# svf.net
KiCad netlist of a schematic drawn in EAGLE
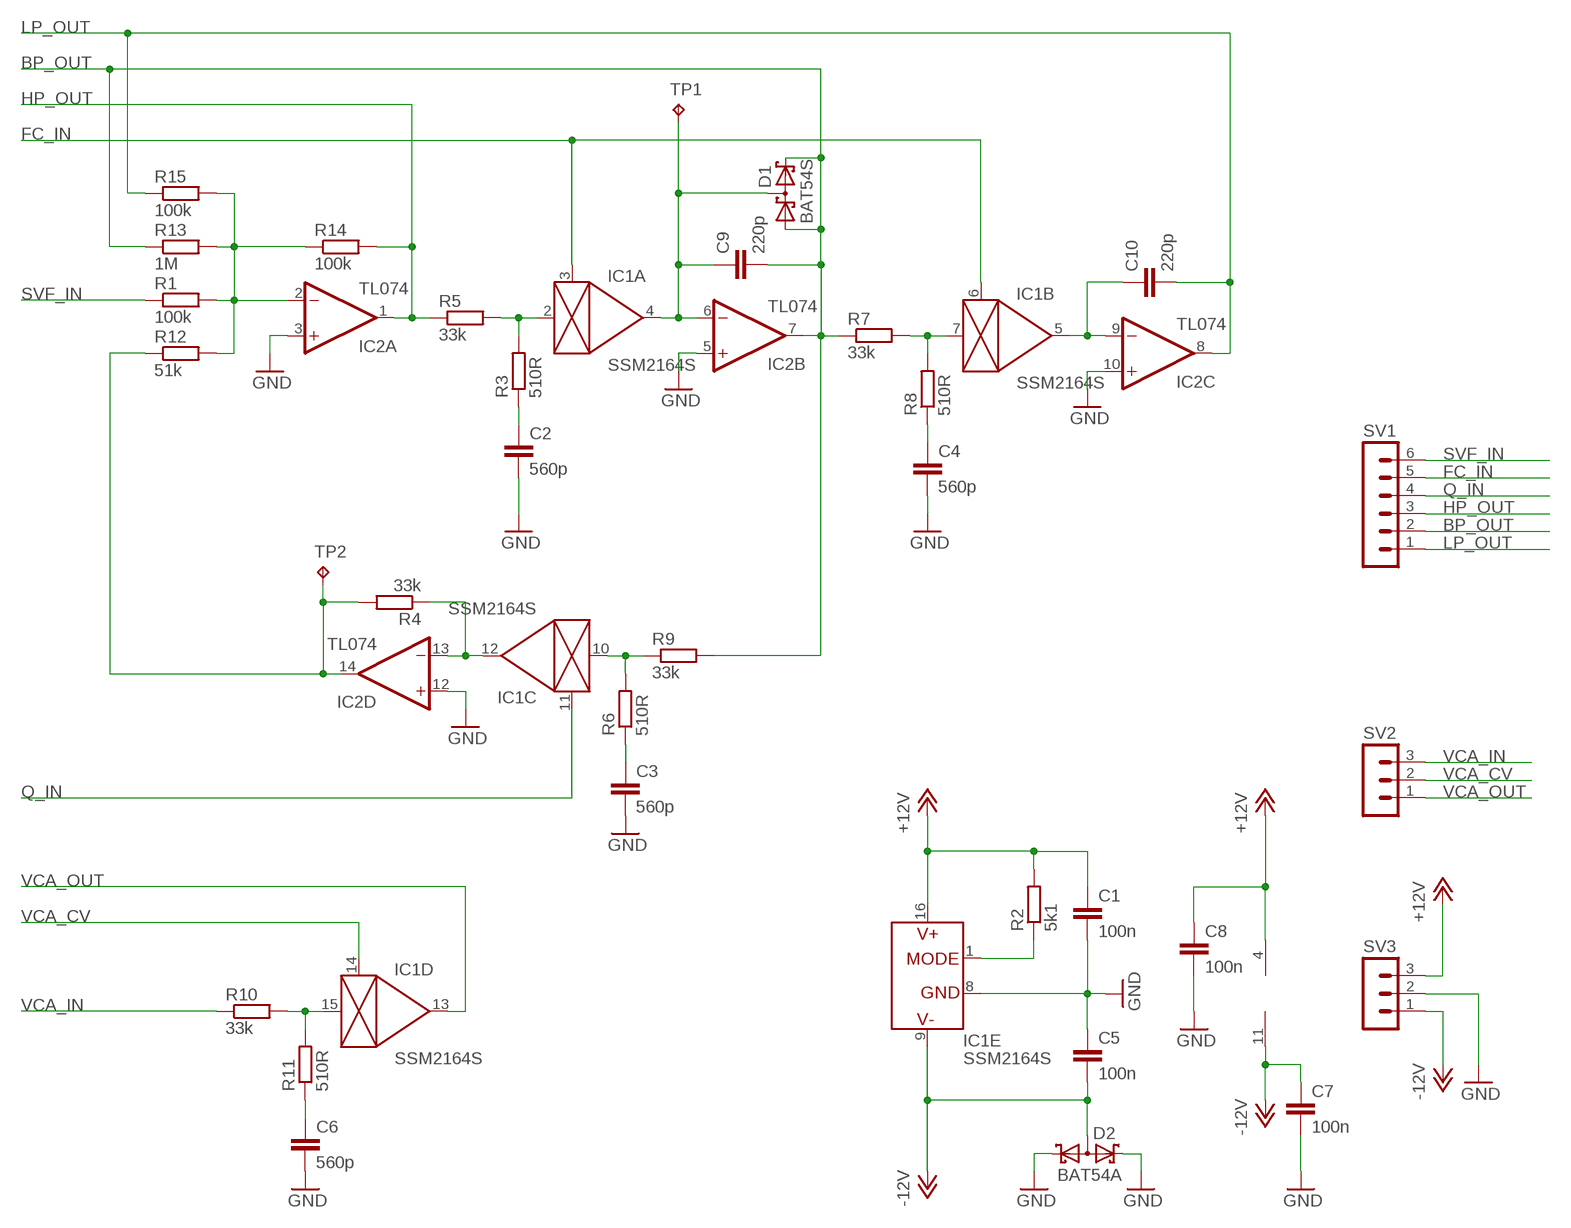
[diagram p0: schematic, sheet 1]

(export (version "E")
  (design (tool "Eeschema 10.0.6"))
  (components
    (comp (ref "C1")
      (value "100n")
      (footprint "eagle-import:C0603")
      (libsource (lib "eagle-import") (part "C-EUC0603"))
    )
    (comp (ref "C2")
      (value "560p")
      (footprint "eagle-import:C0603")
      (libsource (lib "eagle-import") (part "C-EUC0603"))
    )
    (comp (ref "C3")
      (value "560p")
      (footprint "eagle-import:C0603")
      (libsource (lib "eagle-import") (part "C-EUC0603"))
    )
    (comp (ref "C4")
      (value "560p")
      (footprint "eagle-import:C0603")
      (libsource (lib "eagle-import") (part "C-EUC0603"))
    )
    (comp (ref "C5")
      (value "100n")
      (footprint "eagle-import:C0603")
      (libsource (lib "eagle-import") (part "C-EUC0603"))
    )
    (comp (ref "C6")
      (value "560p")
      (footprint "eagle-import:C0603")
      (libsource (lib "eagle-import") (part "C-EUC0603"))
    )
    (comp (ref "C7")
      (value "100n")
      (footprint "eagle-import:C0603")
      (libsource (lib "eagle-import") (part "C-EUC0603"))
    )
    (comp (ref "C8")
      (value "100n")
      (footprint "eagle-import:C0603")
      (libsource (lib "eagle-import") (part "C-EUC0603"))
    )
    (comp (ref "C9")
      (value "220p")
      (footprint "eagle-import:C0603")
      (libsource (lib "eagle-import") (part "C-EUC0603"))
    )
    (comp (ref "C10")
      (value "220p")
      (footprint "eagle-import:C0603")
      (libsource (lib "eagle-import") (part "C-EUC0603"))
    )
    (comp (ref "D1")
      (value "BAT54S")
      (footprint "eagle-import:SOT23")
      (libsource (lib "eagle-import") (part "BAT54S"))
    )
    (comp (ref "D2")
      (value "BAT54A")
      (footprint "eagle-import:SOT23")
      (libsource (lib "eagle-import") (part "BAT54A"))
    )
    (comp (ref "IC1")
      (value "SSM2164S")
      (footprint "eagle-import:SOIC16N")
      (libsource (lib "eagle-import") (part "SSM2164S"))
    )
    (comp (ref "IC2")
      (value "TL074")
      (footprint "eagle-import:SO14")
      (libsource (lib "eagle-import") (part "TL074D"))
    )
    (comp (ref "R1")
      (value "100k")
      (footprint "eagle-import:0603")
      (libsource (lib "eagle-import") (part "R-EU_0603"))
    )
    (comp (ref "R2")
      (value "5k1")
      (footprint "eagle-import:0603")
      (libsource (lib "eagle-import") (part "R-EU_0603"))
    )
    (comp (ref "R3")
      (value "510R")
      (footprint "eagle-import:0603")
      (libsource (lib "eagle-import") (part "R-EU_0603"))
    )
    (comp (ref "R4")
      (value "33k")
      (footprint "eagle-import:0603")
      (libsource (lib "eagle-import") (part "R-EU_0603"))
    )
    (comp (ref "R5")
      (value "33k")
      (footprint "eagle-import:0603")
      (libsource (lib "eagle-import") (part "R-EU_0603"))
    )
    (comp (ref "R6")
      (value "510R")
      (footprint "eagle-import:0603")
      (libsource (lib "eagle-import") (part "R-EU_0603"))
    )
    (comp (ref "R7")
      (value "33k")
      (footprint "eagle-import:0603")
      (libsource (lib "eagle-import") (part "R-EU_0603"))
    )
    (comp (ref "R8")
      (value "510R")
      (footprint "eagle-import:0603")
      (libsource (lib "eagle-import") (part "R-EU_0603"))
    )
    (comp (ref "R9")
      (value "33k")
      (footprint "eagle-import:0603")
      (libsource (lib "eagle-import") (part "R-EU_0603"))
    )
    (comp (ref "R10")
      (value "33k")
      (footprint "eagle-import:0603")
      (libsource (lib "eagle-import") (part "R-EU_0603"))
    )
    (comp (ref "R11")
      (value "510R")
      (footprint "eagle-import:0603")
      (libsource (lib "eagle-import") (part "R-EU_0603"))
    )
    (comp (ref "R12")
      (value "51k")
      (footprint "eagle-import:0603")
      (libsource (lib "eagle-import") (part "R-EU_0603"))
    )
    (comp (ref "R13")
      (value "1M")
      (footprint "eagle-import:0603")
      (libsource (lib "eagle-import") (part "R-EU_0603"))
    )
    (comp (ref "R14")
      (value "100k")
      (footprint "eagle-import:0603")
      (libsource (lib "eagle-import") (part "R-EU_0603"))
    )
    (comp (ref "R15")
      (value "100k")
      (footprint "eagle-import:0603")
      (libsource (lib "eagle-import") (part "R-EU_0603"))
    )
    (comp (ref "SV1")
      (value "MA06-1")
      (footprint "eagle-import:MA06-1")
      (libsource (lib "eagle-import") (part "MA06-1"))
    )
    (comp (ref "SV2")
      (value "MA03-1")
      (footprint "eagle-import:MA03-1")
      (libsource (lib "eagle-import") (part "MA03-1"))
    )
    (comp (ref "SV3")
      (value "MA03-1")
      (footprint "eagle-import:MA03-1")
      (libsource (lib "eagle-import") (part "MA03-1"))
    )
    (comp (ref "TP1")
      (value "TPPAD1-13")
      (footprint "eagle-import:P1-13")
      (libsource (lib "eagle-import") (part "TPPAD1-13"))
    )
    (comp (ref "TP2")
      (value "TPPAD1-13")
      (footprint "eagle-import:P1-13")
      (libsource (lib "eagle-import") (part "TPPAD1-13"))
    )
  )
  (nets
    (net (code "1") (name "+12V") (class "Default")
      (node (ref "C1") (pin "1") (pinfunction "1_1") (pintype "passive"))
      (node (ref "C8") (pin "1") (pinfunction "1_1") (pintype "passive"))
      (node (ref "IC1") (pin "16") (pinfunction "V+_16") (pintype "power_in"))
      (node (ref "IC2") (pin "4") (pinfunction "V+_4") (pintype "power_in"))
      (node (ref "R2") (pin "2") (pinfunction "2_2") (pintype "passive"))
      (node (ref "SV3") (pin "3") (pinfunction "3_3") (pintype "passive"))
    )
    (net (code "2") (name "-12V") (class "Default")
      (node (ref "C5") (pin "2") (pinfunction "2_2") (pintype "passive"))
      (node (ref "C7") (pin "1") (pinfunction "1_1") (pintype "passive"))
      (node (ref "D2") (pin "3") (pinfunction "AA_3") (pintype "passive"))
      (node (ref "IC1") (pin "9") (pinfunction "V-_9") (pintype "power_in"))
      (node (ref "IC2") (pin "11") (pinfunction "V-_11") (pintype "power_in"))
      (node (ref "SV3") (pin "1") (pinfunction "1_1") (pintype "passive"))
    )
    (net (code "3") (name "/BP_OUT") (class "Default")
      (node (ref "C9") (pin "2") (pinfunction "2_2") (pintype "passive"))
      (node (ref "D1") (pin "1") (pinfunction "A1_1") (pintype "passive"))
      (node (ref "D1") (pin "2") (pinfunction "C2_2") (pintype "passive"))
      (node (ref "IC2") (pin "7") (pinfunction "OUT_7") (pintype "output"))
      (node (ref "R13") (pin "1") (pinfunction "1_1") (pintype "passive"))
      (node (ref "R7") (pin "1") (pinfunction "1_1") (pintype "passive"))
      (node (ref "R9") (pin "2") (pinfunction "2_2") (pintype "passive"))
      (node (ref "SV1") (pin "2") (pinfunction "2_2") (pintype "passive"))
    )
    (net (code "4") (name "/FC_IN") (class "Default")
      (node (ref "IC1") (pin "3") (pinfunction "CTRL_3") (pintype "input"))
      (node (ref "IC1") (pin "6") (pinfunction "CTRL_6") (pintype "input"))
      (node (ref "SV1") (pin "5") (pinfunction "5_5") (pintype "passive"))
    )
    (net (code "5") (name "/HP_OUT") (class "Default")
      (node (ref "IC2") (pin "1") (pinfunction "OUT_1") (pintype "output"))
      (node (ref "R14") (pin "2") (pinfunction "2_2") (pintype "passive"))
      (node (ref "R5") (pin "1") (pinfunction "1_1") (pintype "passive"))
      (node (ref "SV1") (pin "3") (pinfunction "3_3") (pintype "passive"))
    )
    (net (code "6") (name "/LP_OUT") (class "Default")
      (node (ref "C10") (pin "2") (pinfunction "2_2") (pintype "passive"))
      (node (ref "IC2") (pin "8") (pinfunction "OUT_8") (pintype "output"))
      (node (ref "R15") (pin "1") (pinfunction "1_1") (pintype "passive"))
      (node (ref "SV1") (pin "1") (pinfunction "1_1") (pintype "passive"))
    )
    (net (code "7") (name "/Q_IN") (class "Default")
      (node (ref "IC1") (pin "11") (pinfunction "CTRL_11") (pintype "input"))
      (node (ref "SV1") (pin "4") (pinfunction "4_4") (pintype "passive"))
    )
    (net (code "8") (name "/SVF_IN") (class "Default")
      (node (ref "R1") (pin "1") (pinfunction "1_1") (pintype "passive"))
      (node (ref "SV1") (pin "6") (pinfunction "6_6") (pintype "passive"))
    )
    (net (code "9") (name "/VCA_CV") (class "Default")
      (node (ref "IC1") (pin "14") (pinfunction "CTRL_14") (pintype "input"))
      (node (ref "SV2") (pin "2") (pinfunction "2_2") (pintype "passive"))
    )
    (net (code "10") (name "/VCA_IN") (class "Default")
      (node (ref "R10") (pin "1") (pinfunction "1_1") (pintype "passive"))
      (node (ref "SV2") (pin "3") (pinfunction "3_3") (pintype "passive"))
    )
    (net (code "11") (name "/VCA_OUT") (class "Default")
      (node (ref "IC1") (pin "13") (pinfunction "OUT_13") (pintype "output"))
      (node (ref "SV2") (pin "1") (pinfunction "1_1") (pintype "passive"))
    )
    (net (code "12") (name "GND") (class "Default")
      (node (ref "C1") (pin "2") (pinfunction "2_2") (pintype "passive"))
      (node (ref "C2") (pin "2") (pinfunction "2_2") (pintype "passive"))
      (node (ref "C3") (pin "2") (pinfunction "2_2") (pintype "passive"))
      (node (ref "C4") (pin "2") (pinfunction "2_2") (pintype "passive"))
      (node (ref "C5") (pin "1") (pinfunction "1_1") (pintype "passive"))
      (node (ref "C6") (pin "2") (pinfunction "2_2") (pintype "passive"))
      (node (ref "C7") (pin "2") (pinfunction "2_2") (pintype "passive"))
      (node (ref "C8") (pin "2") (pinfunction "2_2") (pintype "passive"))
      (node (ref "D2") (pin "1") (pinfunction "K1_1") (pintype "passive"))
      (node (ref "D2") (pin "2") (pinfunction "K2_2") (pintype "passive"))
      (node (ref "IC1") (pin "8") (pinfunction "GND_8") (pintype "power_in"))
      (node (ref "IC2") (pin "10") (pinfunction "+IN_10") (pintype "input"))
      (node (ref "IC2") (pin "12") (pinfunction "+IN_12") (pintype "input"))
      (node (ref "IC2") (pin "3") (pinfunction "+IN_3") (pintype "input"))
      (node (ref "IC2") (pin "5") (pinfunction "+IN_5") (pintype "input"))
      (node (ref "SV3") (pin "2") (pinfunction "2_2") (pintype "passive"))
    )
    (net (code "13") (name "Net-(C2-Pad1)") (class "Default")
      (node (ref "C2") (pin "1") (pinfunction "1_1") (pintype "passive"))
      (node (ref "R3") (pin "1") (pinfunction "1_1") (pintype "passive"))
    )
    (net (code "14") (name "Net-(C3-Pad1)") (class "Default")
      (node (ref "C3") (pin "1") (pinfunction "1_1") (pintype "passive"))
      (node (ref "R6") (pin "1") (pinfunction "1_1") (pintype "passive"))
    )
    (net (code "15") (name "Net-(C4-Pad1)") (class "Default")
      (node (ref "C4") (pin "1") (pinfunction "1_1") (pintype "passive"))
      (node (ref "R8") (pin "1") (pinfunction "1_1") (pintype "passive"))
    )
    (net (code "16") (name "Net-(C6-Pad1)") (class "Default")
      (node (ref "C6") (pin "1") (pinfunction "1_1") (pintype "passive"))
      (node (ref "R11") (pin "1") (pinfunction "1_1") (pintype "passive"))
    )
    (net (code "17") (name "Net-(D1-C1A2)") (class "Default")
      (node (ref "C9") (pin "1") (pinfunction "1_1") (pintype "passive"))
      (node (ref "D1") (pin "3") (pinfunction "C1A2_3") (pintype "passive"))
      (node (ref "IC1") (pin "4") (pinfunction "OUT_4") (pintype "output"))
      (node (ref "IC2") (pin "6") (pinfunction "-IN_6") (pintype "input"))
      (node (ref "TP1") (pin "TP") (pinfunction "TP_TP") (pintype "input"))
    )
    (net (code "18") (name "Net-(IC1A-IN)") (class "Default")
      (node (ref "IC1") (pin "2") (pinfunction "IN_2") (pintype "input"))
      (node (ref "R3") (pin "2") (pinfunction "2_2") (pintype "passive"))
      (node (ref "R5") (pin "2") (pinfunction "2_2") (pintype "passive"))
    )
    (net (code "19") (name "Net-(IC1B-IN)") (class "Default")
      (node (ref "IC1") (pin "7") (pinfunction "IN_7") (pintype "input"))
      (node (ref "R7") (pin "2") (pinfunction "2_2") (pintype "passive"))
      (node (ref "R8") (pin "2") (pinfunction "2_2") (pintype "passive"))
    )
    (net (code "20") (name "Net-(IC1B-OUT)") (class "Default")
      (node (ref "C10") (pin "1") (pinfunction "1_1") (pintype "passive"))
      (node (ref "IC1") (pin "5") (pinfunction "OUT_5") (pintype "output"))
      (node (ref "IC2") (pin "9") (pinfunction "-IN_9") (pintype "input"))
    )
    (net (code "21") (name "Net-(IC1C-IN)") (class "Default")
      (node (ref "IC1") (pin "10") (pinfunction "IN_10") (pintype "input"))
      (node (ref "R6") (pin "2") (pinfunction "2_2") (pintype "passive"))
      (node (ref "R9") (pin "1") (pinfunction "1_1") (pintype "passive"))
    )
    (net (code "22") (name "Net-(IC1C-OUT)") (class "Default")
      (node (ref "IC1") (pin "12") (pinfunction "OUT_12") (pintype "output"))
      (node (ref "IC2") (pin "13") (pinfunction "-IN_13") (pintype "input"))
      (node (ref "R4") (pin "1") (pinfunction "1_1") (pintype "passive"))
    )
    (net (code "23") (name "Net-(IC1D-IN)") (class "Default")
      (node (ref "IC1") (pin "15") (pinfunction "IN_15") (pintype "input"))
      (node (ref "R10") (pin "2") (pinfunction "2_2") (pintype "passive"))
      (node (ref "R11") (pin "2") (pinfunction "2_2") (pintype "passive"))
    )
    (net (code "24") (name "Net-(IC1E-MODE)") (class "Default")
      (node (ref "IC1") (pin "1") (pinfunction "MODE_1") (pintype "input"))
      (node (ref "R2") (pin "1") (pinfunction "1_1") (pintype "passive"))
    )
    (net (code "25") (name "Net-(IC2A--IN)") (class "Default")
      (node (ref "IC2") (pin "2") (pinfunction "-IN_2") (pintype "input"))
      (node (ref "R1") (pin "2") (pinfunction "2_2") (pintype "passive"))
      (node (ref "R12") (pin "2") (pinfunction "2_2") (pintype "passive"))
      (node (ref "R13") (pin "2") (pinfunction "2_2") (pintype "passive"))
      (node (ref "R14") (pin "1") (pinfunction "1_1") (pintype "passive"))
      (node (ref "R15") (pin "2") (pinfunction "2_2") (pintype "passive"))
    )
    (net (code "26") (name "Net-(IC2D-OUT)") (class "Default")
      (node (ref "IC2") (pin "14") (pinfunction "OUT_14") (pintype "output"))
      (node (ref "R12") (pin "1") (pinfunction "1_1") (pintype "passive"))
      (node (ref "R4") (pin "2") (pinfunction "2_2") (pintype "passive"))
      (node (ref "TP2") (pin "TP") (pinfunction "TP_TP") (pintype "input"))
    )
  )
)
